# cpu.net
KiCad netlist of a schematic drawn in Altium Designer
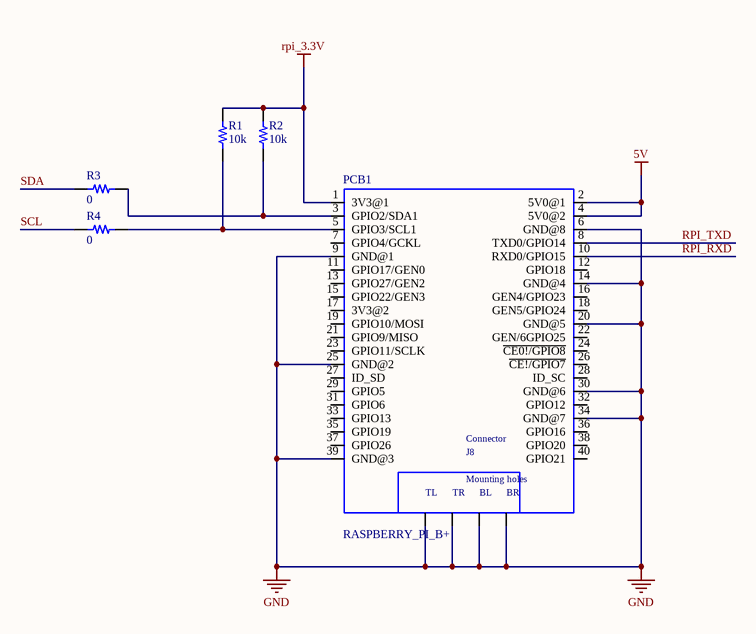
[diagram p0: cpu.SchDoc]

(export (version "E")
  (design (tool "Eeschema 10.0.6"))
  (components
    (comp (ref "PCB1")
      (value "RASPBERRY_PI_B+")
      (footprint "RASPBERRY_PI_B+")
      (description "BCM2835 Raspberry Pi Model B+ - ARM11, VideoCore MPU Embedded Evaluation Board")
      (fields (field (name "MP") "RASPBERRY PI B+") (field (name "MF") "Raspberry Pi"))
      (libsource (lib "RASPBERRY_PI_B_") (part "RASPBERRY_PI_B+"))
    )
    (comp (ref "R1")
      (value "10k")
      (footprint "RES 0603_1608")
      (description "Resistor")
      (fields (field (name "PART NUMBER") "CRCW060329K4FKEA") (field (name "MANUFACTURER") "Vishay Dale"))
      (libsource (lib "Celestial Altium Library - altium_library") (part "Resistor"))
    )
    (comp (ref "R2")
      (value "10k")
      (footprint "RES 0603_1608")
      (description "Resistor")
      (fields (field (name "PART NUMBER") "CRCW060329K4FKEA") (field (name "MANUFACTURER") "Vishay Dale"))
      (libsource (lib "Celestial Altium Library - altium_library") (part "Resistor"))
    )
    (comp (ref "R3")
      (value "0")
      (footprint "RES 0603_1608")
      (description "Resistor")
      (fields (field (name "PART NUMBER") "CRCW060329K4FKEA") (field (name "MANUFACTURER") "Vishay Dale"))
      (libsource (lib "Celestial Altium Library - altium_library") (part "Resistor"))
    )
    (comp (ref "R4")
      (value "0")
      (footprint "RES 0603_1608")
      (description "Resistor")
      (fields (field (name "PART NUMBER") "CRCW060329K4FKEA") (field (name "MANUFACTURER") "Vishay Dale"))
      (libsource (lib "Celestial Altium Library - altium_library") (part "Resistor"))
    )
  )
  (nets
    (net (code "1") (name "/RPI_RXD") (class "Default")
      (node (ref "PCB1") (pin "10") (pinfunction "RXD0/GPIO15_10") (pintype "bidirectional"))
    )
    (net (code "2") (name "/RPI_TXD") (class "Default")
      (node (ref "PCB1") (pin "8") (pinfunction "TXD0/GPIO14_8") (pintype "bidirectional"))
    )
    (net (code "3") (name "/SCL") (class "Default")
      (node (ref "R4") (pin "1") (pinfunction "1_1") (pintype "passive"))
    )
    (net (code "4") (name "/SDA") (class "Default")
      (node (ref "R3") (pin "1") (pinfunction "1_1") (pintype "passive"))
    )
    (net (code "5") (name "5V") (class "Default")
      (node (ref "PCB1") (pin "2") (pinfunction "5V0@1_2") (pintype "power_in"))
      (node (ref "PCB1") (pin "4") (pinfunction "5V0@2_4") (pintype "power_in"))
    )
    (net (code "6") (name "GND") (class "Default")
      (node (ref "PCB1") (pin "14") (pinfunction "GND@4_14") (pintype "power_in"))
      (node (ref "PCB1") (pin "20") (pinfunction "GND@5_20") (pintype "power_in"))
      (node (ref "PCB1") (pin "25") (pinfunction "GND@2_25") (pintype "power_in"))
      (node (ref "PCB1") (pin "30") (pinfunction "GND@6_30") (pintype "power_in"))
      (node (ref "PCB1") (pin "34") (pinfunction "GND@7_34") (pintype "power_in"))
      (node (ref "PCB1") (pin "39") (pinfunction "GND@3_39") (pintype "power_in"))
      (node (ref "PCB1") (pin "6") (pinfunction "GND@8_6") (pintype "power_in"))
      (node (ref "PCB1") (pin "9") (pinfunction "GND@1_9") (pintype "power_in"))
      (node (ref "PCB1") (pin "PE_BL") (pinfunction "BL_PE_BL") (pintype "bidirectional"))
      (node (ref "PCB1") (pin "PE_BR") (pinfunction "BR_PE_BR") (pintype "bidirectional"))
      (node (ref "PCB1") (pin "PE_TL") (pinfunction "TL_PE_TL") (pintype "bidirectional"))
      (node (ref "PCB1") (pin "PE_TR") (pinfunction "TR_PE_TR") (pintype "bidirectional"))
    )
    (net (code "7") (name "Net-(PCB1-GPIO2{slash}SDA1)") (class "Default")
      (node (ref "PCB1") (pin "3") (pinfunction "GPIO2/SDA1_3") (pintype "bidirectional"))
      (node (ref "R2") (pin "2") (pinfunction "2_2") (pintype "passive"))
      (node (ref "R3") (pin "2") (pinfunction "2_2") (pintype "passive"))
    )
    (net (code "8") (name "Net-(PCB1-GPIO3{slash}SCL1)") (class "Default")
      (node (ref "PCB1") (pin "5") (pinfunction "GPIO3/SCL1_5") (pintype "bidirectional"))
      (node (ref "R1") (pin "2") (pinfunction "2_2") (pintype "passive"))
      (node (ref "R4") (pin "2") (pinfunction "2_2") (pintype "passive"))
    )
    (net (code "9") (name "rpi_3.3V") (class "Default")
      (node (ref "PCB1") (pin "1") (pinfunction "3V3@1_1") (pintype "power_in"))
      (node (ref "R1") (pin "1") (pinfunction "1_1") (pintype "passive"))
      (node (ref "R2") (pin "1") (pinfunction "1_1") (pintype "passive"))
    )
    (net (code "10") (name "unconnected-(PCB1-3V3@2-Pad17)") (class "Default")
      (node (ref "PCB1") (pin "17") (pinfunction "3V3@2_17") (pintype "power_in"))
    )
    (net (code "11") (name "unconnected-(PCB1-GEN4{slash}GPIO23-Pad16)") (class "Default")
      (node (ref "PCB1") (pin "16") (pinfunction "GEN4/GPIO23_16") (pintype "bidirectional"))
    )
    (net (code "12") (name "unconnected-(PCB1-GEN5{slash}GPIO24-Pad18)") (class "Default")
      (node (ref "PCB1") (pin "18") (pinfunction "GEN5/GPIO24_18") (pintype "bidirectional"))
    )
    (net (code "13") (name "unconnected-(PCB1-GEN{slash}6GPIO25-Pad22)") (class "Default")
      (node (ref "PCB1") (pin "22") (pinfunction "GEN/6GPIO25_22") (pintype "bidirectional"))
    )
    (net (code "14") (name "unconnected-(PCB1-GPIO4{slash}GCKL-Pad7)") (class "Default")
      (node (ref "PCB1") (pin "7") (pinfunction "GPIO4/GCKL_7") (pintype "bidirectional"))
    )
    (net (code "15") (name "unconnected-(PCB1-GPIO5-Pad29)") (class "Default")
      (node (ref "PCB1") (pin "29") (pinfunction "GPIO5_29") (pintype "bidirectional"))
    )
    (net (code "16") (name "unconnected-(PCB1-GPIO6-Pad31)") (class "Default")
      (node (ref "PCB1") (pin "31") (pinfunction "GPIO6_31") (pintype "bidirectional"))
    )
    (net (code "17") (name "unconnected-(PCB1-GPIO9{slash}MISO-Pad21)") (class "Default")
      (node (ref "PCB1") (pin "21") (pinfunction "GPIO9/MISO_21") (pintype "bidirectional"))
    )
    (net (code "18") (name "unconnected-(PCB1-GPIO10{slash}MOSI-Pad19)") (class "Default")
      (node (ref "PCB1") (pin "19") (pinfunction "GPIO10/MOSI_19") (pintype "bidirectional"))
    )
    (net (code "19") (name "unconnected-(PCB1-GPIO11{slash}SCLK-Pad23)") (class "Default")
      (node (ref "PCB1") (pin "23") (pinfunction "GPIO11/SCLK_23") (pintype "bidirectional"))
    )
    (net (code "20") (name "unconnected-(PCB1-GPIO12-Pad32)") (class "Default")
      (node (ref "PCB1") (pin "32") (pinfunction "GPIO12_32") (pintype "bidirectional"))
    )
    (net (code "21") (name "unconnected-(PCB1-GPIO13-Pad33)") (class "Default")
      (node (ref "PCB1") (pin "33") (pinfunction "GPIO13_33") (pintype "bidirectional"))
    )
    (net (code "22") (name "unconnected-(PCB1-GPIO16-Pad36)") (class "Default")
      (node (ref "PCB1") (pin "36") (pinfunction "GPIO16_36") (pintype "bidirectional"))
    )
    (net (code "23") (name "unconnected-(PCB1-GPIO17{slash}GEN0-Pad11)") (class "Default")
      (node (ref "PCB1") (pin "11") (pinfunction "GPIO17/GEN0_11") (pintype "bidirectional"))
    )
    (net (code "24") (name "unconnected-(PCB1-GPIO18-Pad12)") (class "Default")
      (node (ref "PCB1") (pin "12") (pinfunction "GPIO18_12") (pintype "bidirectional"))
    )
    (net (code "25") (name "unconnected-(PCB1-GPIO19-Pad35)") (class "Default")
      (node (ref "PCB1") (pin "35") (pinfunction "GPIO19_35") (pintype "bidirectional"))
    )
    (net (code "26") (name "unconnected-(PCB1-GPIO20-Pad38)") (class "Default")
      (node (ref "PCB1") (pin "38") (pinfunction "GPIO20_38") (pintype "bidirectional"))
    )
    (net (code "27") (name "unconnected-(PCB1-GPIO21-Pad40)") (class "Default")
      (node (ref "PCB1") (pin "40") (pinfunction "GPIO21_40") (pintype "bidirectional"))
    )
    (net (code "28") (name "unconnected-(PCB1-GPIO22{slash}GEN3-Pad15)") (class "Default")
      (node (ref "PCB1") (pin "15") (pinfunction "GPIO22/GEN3_15") (pintype "bidirectional"))
    )
    (net (code "29") (name "unconnected-(PCB1-GPIO26-Pad37)") (class "Default")
      (node (ref "PCB1") (pin "37") (pinfunction "GPIO26_37") (pintype "bidirectional"))
    )
    (net (code "30") (name "unconnected-(PCB1-GPIO27{slash}GEN2-Pad13)") (class "Default")
      (node (ref "PCB1") (pin "13") (pinfunction "GPIO27/GEN2_13") (pintype "bidirectional"))
    )
    (net (code "31") (name "unconnected-(PCB1-ID_SC-Pad28)") (class "Default")
      (node (ref "PCB1") (pin "28") (pinfunction "ID_SC_28") (pintype "bidirectional"))
    )
    (net (code "32") (name "unconnected-(PCB1-ID_SD-Pad27)") (class "Default")
      (node (ref "PCB1") (pin "27") (pinfunction "ID_SD_27") (pintype "bidirectional"))
    )
    (net (code "33") (name "unconnected-(PCB1-~{CE!{slash}GPIO7}-Pad26)") (class "Default")
      (node (ref "PCB1") (pin "26") (pinfunction "~{CE!/GPIO7}_26") (pintype "bidirectional"))
    )
    (net (code "34") (name "unconnected-(PCB1-~{CE0!{slash}GPIO8}-Pad24)") (class "Default")
      (node (ref "PCB1") (pin "24") (pinfunction "~{CE0!/GPIO8}_24") (pintype "bidirectional"))
    )
  )
)
